# 3_6_1--esp32_-_0730.net
KiCad netlist of a schematic drawn in EasyEDA Pro
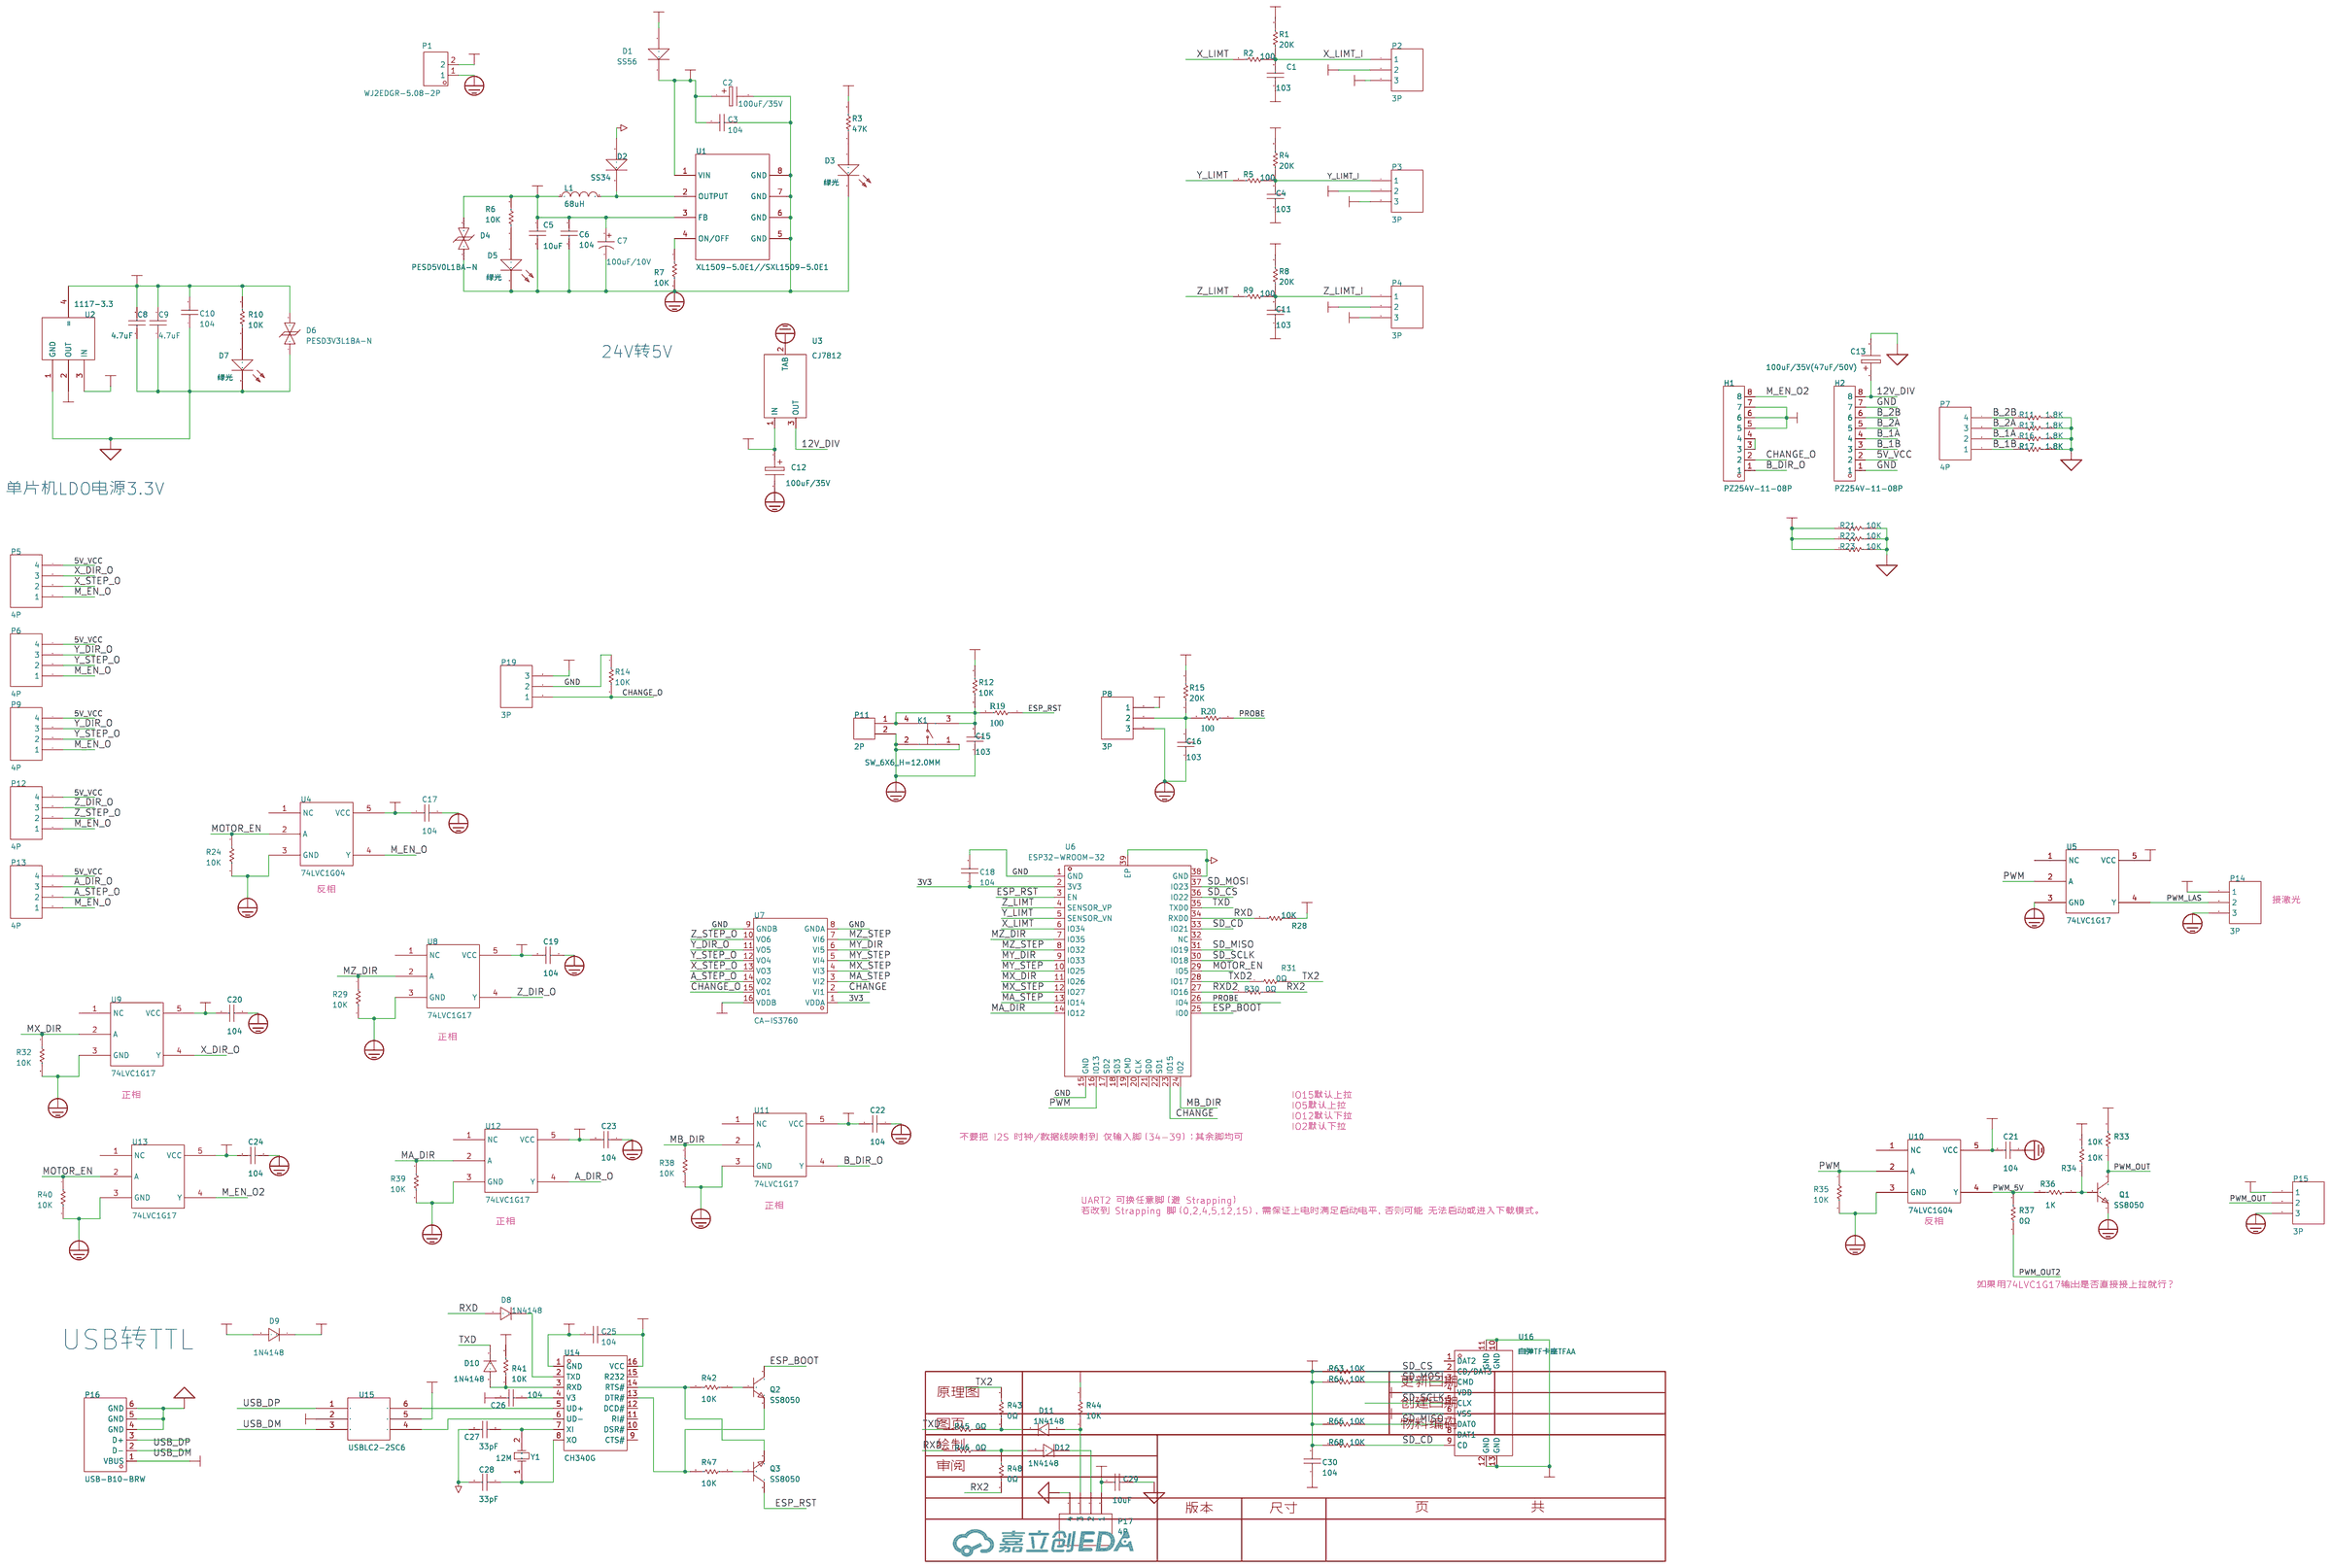
[diagram p0: schematic sheet]

(export (version "E")
  (design (tool "Eeschema 10.0.6"))
  (components
    (comp (ref "C1") (value "103") (footprint "easyedapro:11") (libsource (lib "easyedapro") (part "CAP")))
    (comp (ref "C2")
      (value "100uF/35V")
      (footprint "easyedapro:电解电容贴片10x10")
      (libsource (lib "easyedapro") (part "ELECTRO1"))
    )
    (comp (ref "C3")
      (value "104")
      (footprint "easyedapro:0603C")
      (description "Capacitor (Semiconductor SIM Model)")
      (libsource (lib "easyedapro") (part "Cap Semi"))
    )
    (comp (ref "C4") (value "103") (footprint "easyedapro:11") (libsource (lib "easyedapro") (part "CAP")))
    (comp (ref "C5") (value "10uF") (libsource (lib "") (part "CAP_1")))
    (comp (ref "C6")
      (value "104")
      (footprint "easyedapro:0603C")
      (description "Capacitor (Semiconductor SIM Model)")
      (libsource (lib "easyedapro") (part "Cap Semi"))
    )
    (comp (ref "C7")
      (value "100uF/10V")
      (footprint "easyedapro:CAP-SMD_BD5.0-L5.3-W5.3-RD")
      (fields (field (name "Manufacturer Part") "CS1A101M-CRD54") (field (name "Manufacturer") "ST(先科)"))
      (libsource (lib "easyedapro") (part "CS1A101M-CRD54"))
    )
    (comp (ref "C8") (value "4.7uF") (libsource (lib "") (part "CAP_1")))
    (comp (ref "C9") (value "4.7uF") (libsource (lib "") (part "CAP_1")))
    (comp (ref "C10")
      (value "104")
      (footprint "easyedapro:0603C")
      (description "Capacitor (Semiconductor SIM Model)")
      (libsource (lib "easyedapro") (part "Cap Semi"))
    )
    (comp (ref "C11") (value "103") (footprint "easyedapro:11") (libsource (lib "easyedapro") (part "CAP")))
    (comp (ref "C12")
      (value "100uF/35V")
      (footprint "easyedapro:电解电容贴片10x10")
      (libsource (lib "easyedapro") (part "ELECTRO1"))
    )
    (comp (ref "C13")
      (value "100uF/35V(47uF/50V)")
      (footprint "easyedapro:电解电容贴片10x10")
      (libsource (lib "easyedapro") (part "ELECTRO1"))
    )
    (comp (ref "C15") (value "103") (footprint "easyedapro:11") (libsource (lib "easyedapro") (part "CAP")))
    (comp (ref "C16") (value "103") (footprint "easyedapro:11") (libsource (lib "easyedapro") (part "CAP")))
    (comp (ref "C17")
      (value "104")
      (footprint "easyedapro:0603C")
      (description "Capacitor (Semiconductor SIM Model)")
      (libsource (lib "easyedapro") (part "Cap Semi"))
    )
    (comp (ref "C18")
      (value "104")
      (footprint "easyedapro:0603C")
      (description "Capacitor (Semiconductor SIM Model)")
      (libsource (lib "easyedapro") (part "Cap Semi"))
    )
    (comp (ref "C19")
      (value "104")
      (footprint "easyedapro:0603C")
      (description "Capacitor (Semiconductor SIM Model)")
      (libsource (lib "easyedapro") (part "Cap Semi"))
    )
    (comp (ref "C20")
      (value "104")
      (footprint "easyedapro:0603C")
      (description "Capacitor (Semiconductor SIM Model)")
      (libsource (lib "easyedapro") (part "Cap Semi"))
    )
    (comp (ref "C21")
      (value "104")
      (footprint "easyedapro:0603C")
      (description "Capacitor (Semiconductor SIM Model)")
      (libsource (lib "easyedapro") (part "Cap Semi"))
    )
    (comp (ref "C22")
      (value "104")
      (footprint "easyedapro:0603C")
      (description "Capacitor (Semiconductor SIM Model)")
      (libsource (lib "easyedapro") (part "Cap Semi"))
    )
    (comp (ref "C23")
      (value "104")
      (footprint "easyedapro:0603C")
      (description "Capacitor (Semiconductor SIM Model)")
      (libsource (lib "easyedapro") (part "Cap Semi"))
    )
    (comp (ref "C24")
      (value "104")
      (footprint "easyedapro:0603C")
      (description "Capacitor (Semiconductor SIM Model)")
      (libsource (lib "easyedapro") (part "Cap Semi"))
    )
    (comp (ref "C25")
      (value "104")
      (footprint "easyedapro:0603C")
      (description "Capacitor (Semiconductor SIM Model)")
      (libsource (lib "easyedapro") (part "Cap Semi"))
    )
    (comp (ref "C26")
      (value "104")
      (footprint "easyedapro:0603C")
      (description "Capacitor (Semiconductor SIM Model)")
      (libsource (lib "easyedapro") (part "Cap Semi"))
    )
    (comp (ref "C27")
      (value "18pF")
      (footprint "easyedapro:0603C")
      (description "Capacitor (Semiconductor SIM Model)")
      (libsource (lib "easyedapro") (part "Cap Semi"))
    )
    (comp (ref "C28")
      (value "18pF")
      (footprint "easyedapro:0603C")
      (description "Capacitor (Semiconductor SIM Model)")
      (libsource (lib "easyedapro") (part "Cap Semi"))
    )
    (comp (ref "C29") (value "10uF") (libsource (lib "") (part "CAP_1")))
    (comp (ref "C30")
      (value "104")
      (footprint "easyedapro:11")
      (description "Capacitor (Semiconductor SIM Model)")
      (libsource (lib "easyedapro") (part "Cap Semi"))
    )
    (comp (ref "D1") (value "SS56") (footprint "easyedapro:SMA") (libsource (lib "") (part "1N4148_1")))
    (comp (ref "D2") (value "SS34") (libsource (lib "easyedapro") (part "1N4148")))
    (comp (ref "D3")
      (value "绿光")
      (footprint "easyedapro:0603LED")
      (libsource (lib "easyedapro") (part "LED"))
    )
    (comp (ref "D4")
      (value "PESD5V0L1BA-N")
      (footprint "easyedapro:SOD-523_L1.2-W0.8-LS1.6-BI")
      (description "极性:Bidirectional;反向关断电压（典型值）:5V (Max);击穿电压（最小值）:6V;箝位电压:15V;峰值脉冲电流（10/1000us）:5A (8/20us);")
      (fields (field (name "Manufacturer") "BORN伯恩半导体"))
      (libsource (lib "easyedapro") (part "PESD5V0S1BBN"))
    )
    (comp (ref "D5")
      (value "绿光")
      (footprint "easyedapro:0603LED")
      (libsource (lib "easyedapro") (part "LED"))
    )
    (comp (ref "D6")
      (value "PESD3V3L1BA-N")
      (footprint "easyedapro:SOD-523_L1.2-W0.8-LS1.6-BI")
      (description "极性:Bidirectional;反向关断电压（典型值）:5V (Max);击穿电压（最小值）:6V;箝位电压:15V;峰值脉冲电流（10/1000us）:5A (8/20us);")
      (fields (field (name "Manufacturer") "BORN伯恩半导体"))
      (libsource (lib "easyedapro") (part "PESD5V0S1BBN"))
    )
    (comp (ref "D7")
      (value "绿光")
      (footprint "easyedapro:0603LED")
      (libsource (lib "easyedapro") (part "LED"))
    )
    (comp (ref "D8")
      (value "1N4148")
      (footprint "easyedapro:SOD-123_L2.8-W1.8-LS3.7-RD")
      (fields (field (name "Manufacturer") "MCC(美微科)"))
      (libsource (lib "easyedapro") (part "1N4148W-TP"))
    )
    (comp (ref "D9")
      (value "1N4148")
      (footprint "easyedapro:SOD-123_L2.8-W1.8-LS3.7-RD")
      (fields (field (name "Manufacturer") "MCC(美微科)"))
      (libsource (lib "easyedapro") (part "1N4148W-TP"))
    )
    (comp (ref "D10")
      (value "1N4148")
      (footprint "easyedapro:SOD-123_L2.8-W1.8-LS3.7-RD")
      (fields (field (name "Manufacturer") "MCC(美微科)"))
      (libsource (lib "easyedapro") (part "1N4148W-TP"))
    )
    (comp (ref "D11")
      (value "1N4148")
      (footprint "easyedapro:SOD-123_L2.8-W1.8-LS3.7-RD")
      (fields (field (name "Manufacturer") "MCC(美微科)"))
      (libsource (lib "easyedapro") (part "1N4148W-TP"))
    )
    (comp (ref "D12")
      (value "1N4148")
      (footprint "easyedapro:SOD-123_L2.8-W1.8-LS3.7-RD")
      (fields (field (name "Manufacturer") "MCC(美微科)"))
      (libsource (lib "easyedapro") (part "1N4148W-TP"))
    )
    (comp (ref "H1")
      (value "PZ254V-11-08P")
      (footprint "easyedapro:HDR-TH_8P-P2.54-V-M")
      (fields (field (name "Manufacturer") "XFCN(兴飞)"))
      (libsource (lib "easyedapro") (part "PZ254V-11-08P"))
    )
    (comp (ref "H2")
      (value "PZ254V-11-08P")
      (footprint "easyedapro:HDR-TH_8P-P2.54-V-M")
      (fields (field (name "Manufacturer") "XFCN(兴飞)"))
      (libsource (lib "easyedapro") (part "PZ254V-11-08P"))
    )
    (comp (ref "K1")
      (value "SW_6X6_H=12.0MM")
      (footprint "easyedapro:KEY-SMD_4P-L6.0-W6.0-P4.50-LS9.0")
      (libsource (lib "easyedapro") (part "SW_6X6_H=12.0MM"))
    )
    (comp (ref "L1")
      (value "68uH")
      (footprint "easyedapro:IND-SMD_L7.0-W7.0_SMDRI74-330MT")
      (description "电感值:33uH;精度:±20%;额定电流:960mA;饱和电流(Isat):1.8A;类型:屏蔽电感;")
      (fields (field (name "Manufacturer Part") "SMDRI74-330MT") (field (name "Manufacturer") "SXN(顺翔诺)"))
      (libsource (lib "easyedapro") (part "SMDRI74-330MT"))
    )
    (comp (ref "P1")
      (value "WJ2EDGR-5.08-2P")
      (footprint "easyedapro:CONN-TH_WJ2EDGR-5.08-2P")
      (description "每排PIN数:2;安装方式:弯针;排数:1;间距:5.08mm;连接器类型:板端/插座-开口;")
      (fields (field (name "Manufacturer") "KANGNEX(康奈克斯电气)"))
      (libsource (lib "easyedapro") (part "WJ2EDGR-5.08-2P"))
    )
    (comp (ref "P2")
      (value "3P")
      (footprint "easyedapro:HDR1X3_CON")
      (libsource (lib "easyedapro") (part "3P"))
    )
    (comp (ref "P3")
      (value "3P")
      (footprint "easyedapro:HDR1X3_CON")
      (libsource (lib "easyedapro") (part "3P"))
    )
    (comp (ref "P4")
      (value "3P")
      (footprint "easyedapro:HDR1X3_CON")
      (libsource (lib "easyedapro") (part "3P"))
    )
    (comp (ref "P5")
      (value "4P")
      (footprint "easyedapro:HDR1X4_CON")
      (libsource (lib "easyedapro") (part "4P"))
    )
    (comp (ref "P6")
      (value "4P")
      (footprint "easyedapro:HDR1X4_CON")
      (libsource (lib "easyedapro") (part "4P"))
    )
    (comp (ref "P7")
      (value "4P")
      (footprint "easyedapro:HDR1X4_CON")
      (libsource (lib "easyedapro") (part "4P"))
    )
    (comp (ref "P8")
      (value "3P")
      (footprint "easyedapro:HDR1X3_CON")
      (libsource (lib "easyedapro") (part "3P"))
    )
    (comp (ref "P9")
      (value "4P")
      (footprint "easyedapro:HDR1X4_CON")
      (libsource (lib "easyedapro") (part "4P"))
    )
    (comp (ref "P11") (value "2P") (libsource (lib "easyedapro") (part "2P")))
    (comp (ref "P12")
      (value "4P")
      (footprint "easyedapro:HDR1X4_CON")
      (libsource (lib "easyedapro") (part "4P"))
    )
    (comp (ref "P13")
      (value "4P")
      (footprint "easyedapro:HDR1X4_CON")
      (libsource (lib "easyedapro") (part "4P"))
    )
    (comp (ref "P14")
      (value "3P")
      (footprint "easyedapro:HDR1X3_CON")
      (libsource (lib "easyedapro") (part "3P"))
    )
    (comp (ref "P15")
      (value "3P")
      (footprint "easyedapro:HDR1X3_CON")
      (libsource (lib "easyedapro") (part "3P"))
    )
    (comp (ref "P16")
      (value "USB-B10-BRW")
      (footprint "easyedapro:USB-B-TH_USB-B10-BRW")
      (fields (field (name "Manufacturer") "XUNPU(讯普)"))
      (libsource (lib "easyedapro") (part "USB-B10-BRW"))
    )
    (comp (ref "P17")
      (value "4P")
      (footprint "easyedapro:HDR1X4_CON")
      (libsource (lib "easyedapro") (part "4P"))
    )
    (comp (ref "P19")
      (value "3P")
      (footprint "easyedapro:HDR1X3_CON")
      (libsource (lib "easyedapro") (part "3P"))
    )
    (comp (ref "Q1")
      (value "SS8050")
      (footprint "easyedapro:SOT-23-3_L2.9-W1.3-P1.90-LS2.4-BR")
      (fields (field (name "Manufacturer") "CJ（江苏长电/长晶）"))
      (libsource (lib "easyedapro") (part "SS8050_C2150"))
    )
    (comp (ref "Q2")
      (value "SS8050")
      (footprint "easyedapro:SOT-23-3_L2.9-W1.3-P1.90-LS2.4-BR")
      (fields (field (name "Manufacturer") "Doeshare(德芯)"))
      (libsource (lib "easyedapro") (part "SS8050_C2931717"))
    )
    (comp (ref "Q3")
      (value "SS8050")
      (footprint "easyedapro:SOT-23-3_L2.9-W1.3-P1.90-LS2.4-BR")
      (fields (field (name "Manufacturer") "Doeshare(德芯)"))
      (libsource (lib "easyedapro") (part "SS8050_C2931717"))
    )
    (comp (ref "R1")
      (value "20K")
      (footprint "easyedapro:10")
      (description "Resistor")
      (libsource (lib "") (part "RES_1"))
    )
    (comp (ref "R2")
      (value "100")
      (footprint "easyedapro:10")
      (description "Resistor")
      (libsource (lib "") (part "RES_1"))
    )
    (comp (ref "R3")
      (value "47K")
      (footprint "easyedapro:0603R")
      (description "Resistor")
      (libsource (lib "") (part "RES_1"))
    )
    (comp (ref "R4")
      (value "20K")
      (footprint "easyedapro:10")
      (description "Resistor")
      (libsource (lib "") (part "RES_1"))
    )
    (comp (ref "R5")
      (value "100")
      (footprint "easyedapro:10")
      (description "Resistor")
      (libsource (lib "") (part "RES_1"))
    )
    (comp (ref "R6")
      (value "10K")
      (footprint "easyedapro:0603R")
      (description "Resistor")
      (libsource (lib "") (part "RES_1"))
    )
    (comp (ref "R7")
      (value "10K")
      (footprint "easyedapro:0603R")
      (description "Resistor")
      (libsource (lib "") (part "RES_1"))
    )
    (comp (ref "R8")
      (value "20K")
      (footprint "easyedapro:10")
      (description "Resistor")
      (libsource (lib "") (part "RES_1"))
    )
    (comp (ref "R9")
      (value "100")
      (footprint "easyedapro:10")
      (description "Resistor")
      (libsource (lib "") (part "RES_1"))
    )
    (comp (ref "R10")
      (value "10K")
      (footprint "easyedapro:0603R")
      (description "Resistor")
      (libsource (lib "") (part "RES_1"))
    )
    (comp (ref "R11")
      (value "10K")
      (footprint "easyedapro:0603R")
      (description "Resistor")
      (libsource (lib "easyedapro") (part "10K"))
    )
    (comp (ref "R12")
      (value "10K")
      (footprint "easyedapro:0603R")
      (description "Resistor")
      (libsource (lib "") (part "RES_1"))
    )
    (comp (ref "R13")
      (value "10K")
      (footprint "easyedapro:0603R")
      (description "Resistor")
      (libsource (lib "easyedapro") (part "10K"))
    )
    (comp (ref "R14")
      (value "10K")
      (footprint "easyedapro:0603R")
      (description "Resistor")
      (libsource (lib "") (part "RES_1"))
    )
    (comp (ref "R15")
      (value "10K")
      (footprint "easyedapro:0603R")
      (description "Resistor")
      (libsource (lib "") (part "RES_1"))
    )
    (comp (ref "R16")
      (value "10K")
      (footprint "easyedapro:0603R")
      (description "Resistor")
      (libsource (lib "easyedapro") (part "10K"))
    )
    (comp (ref "R17")
      (value "10K")
      (footprint "easyedapro:0603R")
      (description "Resistor")
      (libsource (lib "easyedapro") (part "10K"))
    )
    (comp (ref "R19")
      (value "100")
      (description "Resistor")
      (fields (field (name "Publisher") "Altium Limited"))
      (libsource (lib "easyedapro") (part "RES"))
    )
    (comp (ref "R20")
      (value "100")
      (description "Resistor")
      (fields (field (name "Publisher") "Altium Limited"))
      (libsource (lib "easyedapro") (part "RES"))
    )
    (comp (ref "R21")
      (value "10K")
      (footprint "easyedapro:0603R")
      (description "Resistor")
      (libsource (lib "easyedapro") (part "10K"))
    )
    (comp (ref "R22")
      (value "10K")
      (footprint "easyedapro:0603R")
      (description "Resistor")
      (libsource (lib "easyedapro") (part "10K"))
    )
    (comp (ref "R23")
      (value "10K")
      (footprint "easyedapro:0603R")
      (description "Resistor")
      (libsource (lib "easyedapro") (part "10K"))
    )
    (comp (ref "R24")
      (value "10K")
      (description "Resistor")
      (fields (field (name "Publisher") "Altium Limited"))
      (libsource (lib "easyedapro") (part "RES"))
    )
    (comp (ref "R28")
      (value "10K")
      (footprint "easyedapro:0603R")
      (description "Resistor")
      (libsource (lib "") (part "RES_1"))
    )
    (comp (ref "R29")
      (value "10K")
      (description "Resistor")
      (fields (field (name "Publisher") "Altium Limited"))
      (libsource (lib "easyedapro") (part "RES"))
    )
    (comp (ref "R30")
      (value "0Ω")
      (description "Resistor")
      (fields (field (name "Publisher") "Altium Limited"))
      (libsource (lib "easyedapro") (part "RES"))
    )
    (comp (ref "R31")
      (value "0Ω")
      (description "Resistor")
      (fields (field (name "Publisher") "Altium Limited"))
      (libsource (lib "easyedapro") (part "RES"))
    )
    (comp (ref "R32")
      (value "10K")
      (description "Resistor")
      (fields (field (name "Publisher") "Altium Limited"))
      (libsource (lib "easyedapro") (part "RES"))
    )
    (comp (ref "R33")
      (value "10K")
      (description "Resistor")
      (fields (field (name "Publisher") "Altium Limited"))
      (libsource (lib "easyedapro") (part "RES"))
    )
    (comp (ref "R34")
      (value "10K")
      (description "Resistor")
      (fields (field (name "Publisher") "Altium Limited"))
      (libsource (lib "easyedapro") (part "RES"))
    )
    (comp (ref "R35")
      (value "10K")
      (description "Resistor")
      (fields (field (name "Publisher") "Altium Limited"))
      (libsource (lib "easyedapro") (part "RES"))
    )
    (comp (ref "R36")
      (value "1K")
      (description "Resistor")
      (fields (field (name "Publisher") "Altium Limited"))
      (libsource (lib "easyedapro") (part "RES"))
    )
    (comp (ref "R37")
      (value "0Ω")
      (description "Resistor")
      (fields (field (name "Publisher") "Altium Limited"))
      (libsource (lib "easyedapro") (part "RES"))
    )
    (comp (ref "R38")
      (value "10K")
      (description "Resistor")
      (fields (field (name "Publisher") "Altium Limited"))
      (libsource (lib "easyedapro") (part "RES"))
    )
    (comp (ref "R39")
      (value "10K")
      (description "Resistor")
      (fields (field (name "Publisher") "Altium Limited"))
      (libsource (lib "easyedapro") (part "RES"))
    )
    (comp (ref "R40")
      (value "10K")
      (description "Resistor")
      (fields (field (name "Publisher") "Altium Limited"))
      (libsource (lib "easyedapro") (part "RES"))
    )
    (comp (ref "R41")
      (value "10K")
      (footprint "easyedapro:0603R")
      (description "Resistor")
      (libsource (lib "") (part "RES_1"))
    )
    (comp (ref "R42")
      (value "10K")
      (footprint "easyedapro:0603R")
      (description "Resistor")
      (libsource (lib "") (part "RES_1"))
    )
    (comp (ref "R43")
      (value "0Ω")
      (description "Resistor")
      (fields (field (name "Publisher") "Altium Limited"))
      (libsource (lib "easyedapro") (part "RES"))
    )
    (comp (ref "R44")
      (value "10K")
      (footprint "easyedapro:0603R")
      (description "Resistor")
      (libsource (lib "") (part "RES_1"))
    )
    (comp (ref "R45")
      (value "0Ω")
      (description "Resistor")
      (fields (field (name "Publisher") "Altium Limited"))
      (libsource (lib "easyedapro") (part "RES"))
    )
    (comp (ref "R46")
      (value "0Ω")
      (description "Resistor")
      (fields (field (name "Publisher") "Altium Limited"))
      (libsource (lib "easyedapro") (part "RES"))
    )
    (comp (ref "R47")
      (value "10K")
      (footprint "easyedapro:0603R")
      (description "Resistor")
      (libsource (lib "") (part "RES_1"))
    )
    (comp (ref "R48")
      (value "0Ω")
      (description "Resistor")
      (fields (field (name "Publisher") "Altium Limited"))
      (libsource (lib "easyedapro") (part "RES"))
    )
    (comp (ref "R63")
      (value "10K")
      (footprint "easyedapro:10")
      (description "Resistor")
      (libsource (lib "") (part "RES_1"))
    )
    (comp (ref "R64")
      (value "10K")
      (footprint "easyedapro:10")
      (description "Resistor")
      (libsource (lib "") (part "RES_1"))
    )
    (comp (ref "R66")
      (value "10K")
      (footprint "easyedapro:10")
      (description "Resistor")
      (libsource (lib "") (part "RES_1"))
    )
    (comp (ref "R68")
      (value "10K")
      (footprint "easyedapro:10")
      (description "Resistor")
      (libsource (lib "") (part "RES_1"))
    )
    (comp (ref "U1")
      (value "XL1509-5.0E1//SXL1509-5.0E1")
      (footprint "easyedapro:SOIC-8_L5.0-W4.0-P1.27-LS6.0-BL")
      (description "功能类型:降压型;同步整流:-;输出通道数:-;拓扑结构:-;输入电压:-;输出电流(最大值):-;开关频率:-;")
      (fields (field (name "Manufacturer") "XLSEMI(芯龙)"))
      (libsource (lib "easyedapro") (part "XL1509-5.0E1"))
    )
    (comp (ref "U2")
      (value "1117-3.3")
      (footprint "easyedapro:SOT-223")
      (libsource (lib "easyedapro") (part "LM1117"))
    )
    (comp (ref "U3")
      (value "CJ7812")
      (footprint "easyedapro:TO-263-2_L10.1-W9.1-P5.08-LS15.2-TL")
      (description "输出类型:固定;工作电压:35V;输出电压:12V;输出电流:1.5A;电源纹波抑制比(PSRR):71dB@(120Hz);输出极性:正极;")
      (fields (field (name "Manufacturer") "CJ(江苏长电/长晶)"))
      (libsource (lib "easyedapro") (part "CJ7812_C145151"))
    )
    (comp (ref "U4")
      (value "74LVC1G04")
      (footprint "easyedapro:SMD8")
      (libsource (lib "easyedapro") (part "74LVC1G04"))
    )
    (comp (ref "U5")
      (value "74LVC1G17")
      (footprint "easyedapro:SMD8")
      (libsource (lib "easyedapro") (part "74LVC1G04"))
    )
    (comp (ref "U6")
      (value "ESP32-WROOM-32")
      (footprint "easyedapro:WIFIM-SMD_ESP-WROOM-32")
      (description "WiFi+双模蓝牙 双核CPU 网口 顶配MCU 低功耗蓝牙 ESP32系列ESP-WROOM-32模组/ESP-32S 4MB")
      (fields (field (name "Manufacturer") "ESPRESSIF(乐鑫)"))
      (libsource (lib "easyedapro") (part "ESP-WROOM-32"))
    )
    (comp (ref "U7")
      (value "CA-IS3760")
      (footprint "easyedapro:SOIC-16_L9.9-W3.9-P1.27-LS6.0-BL")
      (fields (field (name "Manufacturer") "Chipanalog(川土微)"))
      (libsource (lib "easyedapro") (part "CA-IS3760HN"))
    )
    (comp (ref "U8")
      (value "74LVC1G17")
      (footprint "easyedapro:SMD8")
      (libsource (lib "easyedapro") (part "74LVC1G04"))
    )
    (comp (ref "U9")
      (value "74LVC1G17")
      (footprint "easyedapro:SMD8")
      (libsource (lib "easyedapro") (part "74LVC1G04"))
    )
    (comp (ref "U10")
      (value "74LVC1G04")
      (footprint "easyedapro:SMD8")
      (libsource (lib "easyedapro") (part "74LVC1G04"))
    )
    (comp (ref "U11")
      (value "74LVC1G17")
      (footprint "easyedapro:SMD8")
      (libsource (lib "easyedapro") (part "74LVC1G04"))
    )
    (comp (ref "U12")
      (value "74LVC1G17")
      (footprint "easyedapro:SMD8")
      (libsource (lib "easyedapro") (part "74LVC1G04"))
    )
    (comp (ref "U13")
      (value "74LVC1G17")
      (footprint "easyedapro:SMD8")
      (libsource (lib "easyedapro") (part "74LVC1G04"))
    )
    (comp (ref "U14")
      (value "CH340G")
      (footprint "easyedapro:SOIC-16_L9.9-W3.9-P1.27-LS6.0-BL")
      (description "应用功能:收发器;接口协议:USB 2.0;数据速率:2Mbps;")
      (fields (field (name "Manufacturer") "WCH(南京沁恒)"))
      (libsource (lib "easyedapro") (part "CH340G"))
    )
    (comp (ref "U15")
      (value "USBLC2-2SC6")
      (footprint "easyedapro:SOT-23-6")
      (libsource (lib "easyedapro") (part "DIP6"))
    )
    (comp (ref "U16")
      (value "自弹TF卡座TFAA")
      (footprint "easyedapro:SIM-SMD_C9900015645")
      (libsource (lib "easyedapro") (part "自弹TF卡座TFAA"))
    )
    (comp (ref "Y1")
      (value "12M")
      (footprint "easyedapro:晶振贴片49SSMD")
      (description "Crystal Oscillator")
      (libsource (lib "easyedapro") (part "XTAL"))
    )
  )
  (nets
    (net (code "1") (name "/12V_DIV") (class "Default")
      (node (ref "C13") (pin "1") (pintype "unspecified"))
      (node (ref "H2") (pin "8") (pinfunction "8_8") (pintype "unspecified"))
      (node (ref "U3") (pin "3") (pinfunction "OUT_3") (pintype "unspecified"))
    )
    (net (code "2") (name "/A_DIR_O") (class "Default")
      (node (ref "P13") (pin "3") (pinfunction "3_3") (pintype "unspecified"))
      (node (ref "U12") (pin "4") (pinfunction "Y_4") (pintype "unspecified"))
    )
    (net (code "3") (name "/A_STEP_O") (class "Default")
      (node (ref "P13") (pin "2") (pinfunction "2_2") (pintype "unspecified"))
      (node (ref "U7") (pin "14") (pinfunction "VO2_14") (pintype "unspecified"))
    )
    (net (code "4") (name "/B_1A") (class "Default")
      (node (ref "H2") (pin "4") (pinfunction "4_4") (pintype "unspecified"))
      (node (ref "P7") (pin "2") (pinfunction "2_2") (pintype "unspecified"))
      (node (ref "R16") (pin "1") (pinfunction "1_1") (pintype "unspecified"))
    )
    (net (code "5") (name "/B_1B") (class "Default")
      (node (ref "H2") (pin "3") (pinfunction "3_3") (pintype "unspecified"))
      (node (ref "P7") (pin "1") (pinfunction "1_1") (pintype "unspecified"))
      (node (ref "R17") (pin "1") (pinfunction "1_1") (pintype "unspecified"))
    )
    (net (code "6") (name "/B_2A") (class "Default")
      (node (ref "H2") (pin "5") (pinfunction "5_5") (pintype "unspecified"))
      (node (ref "P7") (pin "3") (pinfunction "3_3") (pintype "unspecified"))
      (node (ref "R13") (pin "1") (pinfunction "1_1") (pintype "unspecified"))
    )
    (net (code "7") (name "/B_2B") (class "Default")
      (node (ref "H2") (pin "6") (pinfunction "6_6") (pintype "unspecified"))
      (node (ref "P7") (pin "4") (pinfunction "4_4") (pintype "unspecified"))
      (node (ref "R11") (pin "1") (pinfunction "1_1") (pintype "unspecified"))
    )
    (net (code "8") (name "/B_DIR_O") (class "Default")
      (node (ref "H1") (pin "1") (pinfunction "1_1") (pintype "unspecified"))
      (node (ref "U11") (pin "4") (pinfunction "Y_4") (pintype "unspecified"))
    )
    (net (code "9") (name "/CHANGE") (class "Default")
      (node (ref "U6") (pin "23") (pinfunction "IO15_23") (pintype "unspecified"))
      (node (ref "U7") (pin "2") (pinfunction "VI1_2") (pintype "unspecified"))
    )
    (net (code "10") (name "/CHANGE_O") (class "Default")
      (node (ref "H1") (pin "2") (pinfunction "2_2") (pintype "unspecified"))
      (node (ref "P19") (pin "1") (pinfunction "1_1") (pintype "unspecified"))
      (node (ref "R14") (pin "2") (pinfunction "2_2") (pintype "unspecified"))
      (node (ref "U7") (pin "15") (pinfunction "VO1_15") (pintype "unspecified"))
    )
    (net (code "11") (name "/ESP_BOOT") (class "Default")
      (node (ref "Q2") (pin "3") (pinfunction "C_3") (pintype "unspecified"))
      (node (ref "U6") (pin "25") (pinfunction "IO0_25") (pintype "unspecified"))
    )
    (net (code "12") (name "/ESP_RST") (class "Default")
      (node (ref "Q3") (pin "3") (pinfunction "C_3") (pintype "unspecified"))
      (node (ref "R19") (pin "1") (pinfunction "1_1") (pintype "input"))
      (node (ref "U6") (pin "3") (pinfunction "EN_3") (pintype "unspecified"))
    )
    (net (code "13") (name "/MA_DIR") (class "Default")
      (node (ref "R39") (pin "1") (pinfunction "1_1") (pintype "input"))
      (node (ref "U12") (pin "2") (pinfunction "A_2") (pintype "unspecified"))
      (node (ref "U6") (pin "14") (pinfunction "IO12_14") (pintype "unspecified"))
    )
    (net (code "14") (name "/MA_STEP") (class "Default")
      (node (ref "U6") (pin "13") (pinfunction "IO14_13") (pintype "unspecified"))
      (node (ref "U7") (pin "3") (pinfunction "VI2_3") (pintype "unspecified"))
    )
    (net (code "15") (name "/MB_DIR") (class "Default")
      (node (ref "R38") (pin "1") (pinfunction "1_1") (pintype "input"))
      (node (ref "U11") (pin "2") (pinfunction "A_2") (pintype "unspecified"))
      (node (ref "U6") (pin "24") (pinfunction "IO2_24") (pintype "unspecified"))
    )
    (net (code "16") (name "/MOTOR_EN") (class "Default")
      (node (ref "R24") (pin "1") (pinfunction "1_1") (pintype "input"))
      (node (ref "R40") (pin "1") (pinfunction "1_1") (pintype "input"))
      (node (ref "U13") (pin "2") (pinfunction "A_2") (pintype "unspecified"))
      (node (ref "U4") (pin "2") (pinfunction "A_2") (pintype "unspecified"))
      (node (ref "U6") (pin "29") (pinfunction "IO5_29") (pintype "unspecified"))
    )
    (net (code "17") (name "/MX_DIR") (class "Default")
      (node (ref "R32") (pin "1") (pinfunction "1_1") (pintype "input"))
      (node (ref "U6") (pin "11") (pinfunction "IO26_11") (pintype "unspecified"))
      (node (ref "U9") (pin "2") (pinfunction "A_2") (pintype "unspecified"))
    )
    (net (code "18") (name "/MX_STEP") (class "Default")
      (node (ref "U6") (pin "12") (pinfunction "IO27_12") (pintype "unspecified"))
      (node (ref "U7") (pin "4") (pinfunction "VI3_4") (pintype "unspecified"))
    )
    (net (code "19") (name "/MY_DIR") (class "Default")
      (node (ref "U6") (pin "9") (pinfunction "IO33_9") (pintype "unspecified"))
      (node (ref "U7") (pin "6") (pinfunction "VI5_6") (pintype "unspecified"))
    )
    (net (code "20") (name "/MY_STEP") (class "Default")
      (node (ref "U6") (pin "10") (pinfunction "IO25_10") (pintype "unspecified"))
      (node (ref "U7") (pin "5") (pinfunction "VI4_5") (pintype "unspecified"))
    )
    (net (code "21") (name "/MZ_DIR") (class "Default")
      (node (ref "R29") (pin "1") (pinfunction "1_1") (pintype "input"))
      (node (ref "U6") (pin "7") (pinfunction "IO35_7") (pintype "unspecified"))
      (node (ref "U8") (pin "2") (pinfunction "A_2") (pintype "unspecified"))
    )
    (net (code "22") (name "/MZ_STEP") (class "Default")
      (node (ref "U6") (pin "8") (pinfunction "IO32_8") (pintype "unspecified"))
      (node (ref "U7") (pin "7") (pinfunction "VI6_7") (pintype "unspecified"))
    )
    (net (code "23") (name "/M_EN_O") (class "Default")
      (node (ref "P12") (pin "1") (pinfunction "1_1") (pintype "unspecified"))
      (node (ref "P13") (pin "1") (pinfunction "1_1") (pintype "unspecified"))
      (node (ref "P5") (pin "1") (pinfunction "1_1") (pintype "unspecified"))
      (node (ref "P6") (pin "1") (pinfunction "1_1") (pintype "unspecified"))
      (node (ref "P9") (pin "1") (pinfunction "1_1") (pintype "unspecified"))
      (node (ref "U4") (pin "4") (pinfunction "Y_4") (pintype "unspecified"))
    )
    (net (code "24") (name "/M_EN_O2") (class "Default")
      (node (ref "H1") (pin "8") (pinfunction "8_8") (pintype "unspecified"))
      (node (ref "U13") (pin "4") (pinfunction "Y_4") (pintype "unspecified"))
    )
    (net (code "25") (name "/PROBE") (class "Default")
      (node (ref "R20") (pin "1") (pinfunction "1_1") (pintype "input"))
      (node (ref "U6") (pin "26") (pinfunction "IO4_26") (pintype "unspecified"))
    )
    (net (code "26") (name "/PWM") (class "Default")
      (node (ref "R35") (pin "1") (pinfunction "1_1") (pintype "input"))
      (node (ref "U10") (pin "2") (pinfunction "A_2") (pintype "unspecified"))
      (node (ref "U5") (pin "2") (pinfunction "A_2") (pintype "unspecified"))
      (node (ref "U6") (pin "16") (pinfunction "IO13_16") (pintype "unspecified"))
    )
    (net (code "27") (name "/PWM_5V") (class "Default")
      (node (ref "R36") (pin "1") (pinfunction "1_1") (pintype "input"))
      (node (ref "R37") (pin "2") (pinfunction "2_2") (pintype "input"))
      (node (ref "U10") (pin "4") (pinfunction "Y_4") (pintype "unspecified"))
    )
    (net (code "28") (name "/PWM_LAS") (class "Default")
      (node (ref "P14") (pin "2") (pinfunction "2_2") (pintype "unspecified"))
      (node (ref "U5") (pin "4") (pinfunction "Y_4") (pintype "unspecified"))
    )
    (net (code "29") (name "/PWM_OUT") (class "Default")
      (node (ref "P15") (pin "2") (pinfunction "2_2") (pintype "unspecified"))
      (node (ref "Q1") (pin "3") (pinfunction "C_3") (pintype "input"))
      (node (ref "R33") (pin "1") (pinfunction "1_1") (pintype "input"))
    )
    (net (code "30") (name "/PWM_OUT2") (class "Default")
      (node (ref "R37") (pin "1") (pinfunction "1_1") (pintype "input"))
    )
    (net (code "31") (name "/RX2") (class "Default")
      (node (ref "R30") (pin "2") (pinfunction "2_2") (pintype "input"))
      (node (ref "R48") (pin "1") (pinfunction "1_1") (pintype "input"))
    )
    (net (code "32") (name "/RXD") (class "Default")
      (node (ref "D8") (pin "2") (pinfunction "A_2") (pintype "input"))
      (node (ref "R28") (pin "2") (pinfunction "2_2") (pintype "unspecified"))
      (node (ref "R46") (pin "1") (pinfunction "1_1") (pintype "input"))
      (node (ref "U6") (pin "34") (pinfunction "RXD0_34") (pintype "unspecified"))
    )
    (net (code "33") (name "/RXD2") (class "Default")
      (node (ref "R30") (pin "1") (pinfunction "1_1") (pintype "input"))
      (node (ref "U6") (pin "27") (pinfunction "IO16_27") (pintype "unspecified"))
    )
    (net (code "34") (name "/SD_CD") (class "Default")
      (node (ref "R68") (pin "1") (pinfunction "1_1") (pintype "unspecified"))
      (node (ref "U16") (pin "9") (pinfunction "CD_9") (pintype "unspecified"))
      (node (ref "U6") (pin "33") (pinfunction "IO21_33") (pintype "unspecified"))
    )
    (net (code "35") (name "/SD_CS") (class "Default")
      (node (ref "R63") (pin "1") (pinfunction "1_1") (pintype "unspecified"))
      (node (ref "U16") (pin "2") (pinfunction "CD/DAT3_2") (pintype "unspecified"))
      (node (ref "U6") (pin "36") (pinfunction "IO22_36") (pintype "unspecified"))
    )
    (net (code "36") (name "/SD_MISO") (class "Default")
      (node (ref "R66") (pin "1") (pinfunction "1_1") (pintype "unspecified"))
      (node (ref "U16") (pin "7") (pinfunction "DAT0_7") (pintype "unspecified"))
      (node (ref "U6") (pin "31") (pinfunction "IO19_31") (pintype "unspecified"))
    )
    (net (code "37") (name "/SD_MOSI") (class "Default")
      (node (ref "R64") (pin "1") (pinfunction "1_1") (pintype "unspecified"))
      (node (ref "U16") (pin "3") (pinfunction "CMD_3") (pintype "unspecified"))
      (node (ref "U6") (pin "37") (pinfunction "IO23_37") (pintype "unspecified"))
    )
    (net (code "38") (name "/SD_SCLK") (class "Default")
      (node (ref "U16") (pin "5") (pinfunction "CLX_5") (pintype "unspecified"))
      (node (ref "U6") (pin "30") (pinfunction "IO18_30") (pintype "unspecified"))
    )
    (net (code "39") (name "/TX2") (class "Default")
      (node (ref "R31") (pin "2") (pinfunction "2_2") (pintype "input"))
      (node (ref "R43") (pin "2") (pinfunction "2_2") (pintype "input"))
    )
    (net (code "40") (name "/TXD") (class "Default")
      (node (ref "D10") (pin "1") (pinfunction "c_1") (pintype "input"))
      (node (ref "R45") (pin "1") (pinfunction "1_1") (pintype "input"))
      (node (ref "U6") (pin "35") (pinfunction "TXD0_35") (pintype "unspecified"))
    )
    (net (code "41") (name "/TXD2") (class "Default")
      (node (ref "R31") (pin "1") (pinfunction "1_1") (pintype "input"))
      (node (ref "U6") (pin "28") (pinfunction "IO17_28") (pintype "unspecified"))
    )
    (net (code "42") (name "/USB_DM") (class "Default")
      (node (ref "P16") (pin "2") (pinfunction "D-_2") (pintype "unspecified"))
      (node (ref "U15") (pin "3") (pinfunction "3_3") (pintype "unspecified"))
    )
    (net (code "43") (name "/USB_DP") (class "Default")
      (node (ref "P16") (pin "3") (pinfunction "D+_3") (pintype "unspecified"))
      (node (ref "U15") (pin "1") (pinfunction "1_1") (pintype "unspecified"))
    )
    (net (code "44") (name "/X_DIR_O") (class "Default")
      (node (ref "P5") (pin "3") (pinfunction "3_3") (pintype "unspecified"))
      (node (ref "U9") (pin "4") (pinfunction "Y_4") (pintype "unspecified"))
    )
    (net (code "45") (name "/X_LIMT") (class "Default")
      (node (ref "R2") (pin "2") (pinfunction "2_2") (pintype "unspecified"))
      (node (ref "U6") (pin "6") (pinfunction "IO34_6") (pintype "unspecified"))
    )
    (net (code "46") (name "/X_LIMT_I") (class "Default")
      (node (ref "C1") (pin "2") (pinfunction "2_2") (pintype "unspecified"))
      (node (ref "P2") (pin "1") (pinfunction "1_1") (pintype "unspecified"))
      (node (ref "R1") (pin "1") (pinfunction "1_1") (pintype "unspecified"))
      (node (ref "R2") (pin "1") (pinfunction "1_1") (pintype "unspecified"))
    )
    (net (code "47") (name "/X_STEP_O") (class "Default")
      (node (ref "P5") (pin "2") (pinfunction "2_2") (pintype "unspecified"))
      (node (ref "U7") (pin "13") (pinfunction "VO3_13") (pintype "unspecified"))
    )
    (net (code "48") (name "/Y_DIR_O") (class "Default")
      (node (ref "P6") (pin "3") (pinfunction "3_3") (pintype "unspecified"))
      (node (ref "P9") (pin "3") (pinfunction "3_3") (pintype "unspecified"))
      (node (ref "U7") (pin "11") (pinfunction "VO5_11") (pintype "unspecified"))
    )
    (net (code "49") (name "/Y_LIMT") (class "Default")
      (node (ref "R5") (pin "2") (pinfunction "2_2") (pintype "unspecified"))
      (node (ref "U6") (pin "5") (pinfunction "SENSOR_VN_5") (pintype "unspecified"))
    )
    (net (code "50") (name "/Y_LIMT_I") (class "Default")
      (node (ref "C4") (pin "2") (pinfunction "2_2") (pintype "unspecified"))
      (node (ref "P3") (pin "1") (pinfunction "1_1") (pintype "unspecified"))
      (node (ref "R4") (pin "1") (pinfunction "1_1") (pintype "unspecified"))
      (node (ref "R5") (pin "1") (pinfunction "1_1") (pintype "unspecified"))
    )
    (net (code "51") (name "/Y_STEP_O") (class "Default")
      (node (ref "P6") (pin "2") (pinfunction "2_2") (pintype "unspecified"))
      (node (ref "P9") (pin "2") (pinfunction "2_2") (pintype "unspecified"))
      (node (ref "U7") (pin "12") (pinfunction "VO4_12") (pintype "unspecified"))
    )
    (net (code "52") (name "/Z_DIR_O") (class "Default")
      (node (ref "P12") (pin "3") (pinfunction "3_3") (pintype "unspecified"))
      (node (ref "U8") (pin "4") (pinfunction "Y_4") (pintype "unspecified"))
    )
    (net (code "53") (name "/Z_LIMT") (class "Default")
      (node (ref "R9") (pin "2") (pinfunction "2_2") (pintype "unspecified"))
      (node (ref "U6") (pin "4") (pinfunction "SENSOR_VP_4") (pintype "unspecified"))
    )
    (net (code "54") (name "/Z_LIMT_I") (class "Default")
      (node (ref "C11") (pin "2") (pinfunction "2_2") (pintype "unspecified"))
      (node (ref "P4") (pin "1") (pinfunction "1_1") (pintype "unspecified"))
      (node (ref "R8") (pin "1") (pinfunction "1_1") (pintype "unspecified"))
      (node (ref "R9") (pin "1") (pinfunction "1_1") (pintype "unspecified"))
    )
    (net (code "55") (name "/Z_STEP_O") (class "Default")
      (node (ref "P12") (pin "2") (pinfunction "2_2") (pintype "unspecified"))
      (node (ref "U7") (pin "10") (pinfunction "VO6_10") (pintype "unspecified"))
    )
    (net (code "56") (name "3V3") (class "Default")
      (node (ref "C10") (pin "2") (pinfunction "2_2") (pintype "unspecified"))
      (node (ref "C18") (pin "1") (pinfunction "1_1") (pintype "unspecified"))
      (node (ref "C30") (pin "2") (pinfunction "2_2") (pintype "unspecified"))
      (node (ref "C8") (pin "2") (pinfunction "2_2") (pintype "input"))
      (node (ref "C9") (pin "2") (pinfunction "2_2") (pintype "input"))
      (node (ref "D6") (pin "2") (pinfunction "2_2") (pintype "input"))
      (node (ref "R10") (pin "2") (pinfunction "2_2") (pintype "unspecified"))
      (node (ref "R12") (pin "1") (pinfunction "1_1") (pintype "unspecified"))
      (node (ref "R28") (pin "1") (pinfunction "1_1") (pintype "unspecified"))
      (node (ref "R63") (pin "2") (pinfunction "2_2") (pintype "unspecified"))
      (node (ref "R64") (pin "2") (pinfunction "2_2") (pintype "unspecified"))
      (node (ref "R66") (pin "2") (pinfunction "2_2") (pintype "unspecified"))
      (node (ref "R68") (pin "2") (pinfunction "2_2") (pintype "unspecified"))
      (node (ref "U16") (pin "4") (pinfunction "VDD_4") (pintype "unspecified"))
      (node (ref "U2") (pin "2") (pinfunction "OUT_2") (pintype "unspecified"))
      (node (ref "U2") (pin "4") (pinfunction "=_4") (pintype "unspecified"))
      (node (ref "U6") (pin "2") (pinfunction "3V3_2") (pintype "unspecified"))
      (node (ref "U7") (pin "1") (pinfunction "VDDA_1") (pintype "unspecified"))
    )
    (net (code "57") (name "5V_VCC") (class "Default")
      (node (ref "C17") (pin "2") (pinfunction "2_2") (pintype "unspecified"))
      (node (ref "C19") (pin "2") (pinfunction "2_2") (pintype "unspecified"))
      (node (ref "C20") (pin "2") (pinfunction "2_2") (pintype "unspecified"))
      (node (ref "C21") (pin "2") (pinfunction "2_2") (pintype "unspecified"))
      (node (ref "C22") (pin "2") (pinfunction "2_2") (pintype "unspecified"))
      (node (ref "C23") (pin "2") (pinfunction "2_2") (pintype "unspecified"))
      (node (ref "C24") (pin "2") (pinfunction "2_2") (pintype "unspecified"))
      (node (ref "C25") (pin "1") (pinfunction "1_1") (pintype "unspecified"))
      (node (ref "C29") (pin "1") (pinfunction "1_1") (pintype "input"))
      (node (ref "C5") (pin "1") (pinfunction "1_1") (pintype "input"))
      (node (ref "C6") (pin "2") (pinfunction "2_2") (pintype "unspecified"))
      (node (ref "C7") (pin "1") (pinfunction "1_1") (pintype "input"))
      (node (ref "D4") (pin "2") (pinfunction "2_2") (pintype "input"))
      (node (ref "D9") (pin "1") (pinfunction "c_1") (pintype "input"))
      (node (ref "H1") (pin "5") (pinfunction "5_5") (pintype "unspecified"))
      (node (ref "H1") (pin "6") (pinfunction "6_6") (pintype "unspecified"))
      (node (ref "H1") (pin "7") (pinfunction "7_7") (pintype "unspecified"))
      (node (ref "H2") (pin "2") (pinfunction "2_2") (pintype "unspecified"))
      (node (ref "L1") (pin "1") (pinfunction "1_1") (pintype "unspecified"))
      (node (ref "P12") (pin "4") (pinfunction "4_4") (pintype "unspecified"))
      (node (ref "P13") (pin "4") (pinfunction "4_4") (pintype "unspecified"))
      (node (ref "P15") (pin "1") (pinfunction "1_1") (pintype "unspecified"))
      (node (ref "P17") (pin "1") (pinfunction "1_1") (pintype "unspecified"))
      (node (ref "P19") (pin "3") (pinfunction "3_3") (pintype "unspecified"))
      (node (ref "P2") (pin "3") (pinfunction "3_3") (pintype "unspecified"))
      (node (ref "P3") (pin "3") (pinfunction "3_3") (pintype "unspecified"))
      (node (ref "P4") (pin "3") (pinfunction "3_3") (pintype "unspecified"))
      (node (ref "P5") (pin "4") (pinfunction "4_4") (pintype "unspecified"))
      (node (ref "P6") (pin "4") (pinfunction "4_4") (pintype "unspecified"))
      (node (ref "P8") (pin "1") (pinfunction "1_1") (pintype "unspecified"))
      (node (ref "P9") (pin "4") (pinfunction "4_4") (pintype "unspecified"))
      (node (ref "R1") (pin "2") (pinfunction "2_2") (pintype "unspecified"))
      (node (ref "R15") (pin "1") (pinfunction "1_1") (pintype "unspecified"))
      (node (ref "R21") (pin "1") (pinfunction "1_1") (pintype "unspecified"))
      (node (ref "R22") (pin "1") (pinfunction "1_1") (pintype "unspecified"))
      (node (ref "R23") (pin "1") (pinfunction "1_1") (pintype "unspecified"))
      (node (ref "R33") (pin "2") (pinfunction "2_2") (pintype "input"))
      (node (ref "R34") (pin "2") (pinfunction "2_2") (pintype "input"))
      (node (ref "R4") (pin "2") (pinfunction "2_2") (pintype "unspecified"))
      (node (ref "R41") (pin "2") (pinfunction "2_2") (pintype "unspecified"))
      (node (ref "R44") (pin "2") (pinfunction "2_2") (pintype "unspecified"))
      (node (ref "R6") (pin "2") (pinfunction "2_2") (pintype "unspecified"))
      (node (ref "R8") (pin "2") (pinfunction "2_2") (pintype "unspecified"))
      (node (ref "U1") (pin "3") (pinfunction "FB_3") (pintype "input"))
      (node (ref "U10") (pin "5") (pinfunction "VCC_5") (pintype "unspecified"))
      (node (ref "U11") (pin "5") (pinfunction "VCC_5") (pintype "unspecified"))
      (node (ref "U12") (pin "5") (pinfunction "VCC_5") (pintype "unspecified"))
      (node (ref "U13") (pin "5") (pinfunction "VCC_5") (pintype "unspecified"))
      (node (ref "U14") (pin "16") (pinfunction "VCC_16") (pintype "unspecified"))
      (node (ref "U2") (pin "3") (pinfunction "IN_3") (pintype "unspecified"))
      (node (ref "U4") (pin "5") (pinfunction "VCC_5") (pintype "unspecified"))
      (node (ref "U5") (pin "5") (pinfunction "VCC_5") (pintype "unspecified"))
      (node (ref "U7") (pin "16") (pinfunction "VDDB_16") (pintype "unspecified"))
      (node (ref "U8") (pin "5") (pinfunction "VCC_5") (pintype "unspecified"))
      (node (ref "U9") (pin "5") (pinfunction "VCC_5") (pintype "unspecified"))
    )
    (net (code "58") (name "24V") (class "Default")
      (node (ref "C12") (pin "1") (pintype "unspecified"))
      (node (ref "D1") (pin "1") (pinfunction "1_1") (pintype "unspecified"))
      (node (ref "P1") (pin "2") (pinfunction "2_2") (pintype "input"))
      (node (ref "P14") (pin "1") (pinfunction "1_1") (pintype "unspecified"))
      (node (ref "R3") (pin "2") (pinfunction "2_2") (pintype "unspecified"))
      (node (ref "U3") (pin "1") (pinfunction "IN_1") (pintype "unspecified"))
    )
    (net (code "59") (name "GND") (class "Default")
      (node (ref "C1") (pin "1") (pinfunction "1_1") (pintype "unspecified"))
      (node (ref "C10") (pin "1") (pinfunction "1_1") (pintype "unspecified"))
      (node (ref "C11") (pin "1") (pinfunction "1_1") (pintype "unspecified"))
      (node (ref "C12") (pin "2") (pintype "unspecified"))
      (node (ref "C13") (pin "2") (pintype "unspecified"))
      (node (ref "C15") (pin "1") (pinfunction "1_1") (pintype "unspecified"))
      (node (ref "C16") (pin "1") (pinfunction "1_1") (pintype "unspecified"))
      (node (ref "C17") (pin "1") (pinfunction "1_1") (pintype "unspecified"))
      (node (ref "C18") (pin "2") (pinfunction "2_2") (pintype "unspecified"))
      (node (ref "C19") (pin "1") (pinfunction "1_1") (pintype "unspecified"))
      (node (ref "C2") (pin "2") (pintype "unspecified"))
      (node (ref "C20") (pin "1") (pinfunction "1_1") (pintype "unspecified"))
      (node (ref "C21") (pin "1") (pinfunction "1_1") (pintype "unspecified"))
      (node (ref "C22") (pin "1") (pinfunction "1_1") (pintype "unspecified"))
      (node (ref "C23") (pin "1") (pinfunction "1_1") (pintype "unspecified"))
      (node (ref "C24") (pin "1") (pinfunction "1_1") (pintype "unspecified"))
      (node (ref "C25") (pin "2") (pinfunction "2_2") (pintype "unspecified"))
      (node (ref "C26") (pin "2") (pinfunction "2_2") (pintype "unspecified"))
      (node (ref "C27") (pin "2") (pinfunction "2_2") (pintype "unspecified"))
      (node (ref "C28") (pin "2") (pinfunction "2_2") (pintype "unspecified"))
      (node (ref "C29") (pin "2") (pinfunction "2_2") (pintype "input"))
      (node (ref "C3") (pin "1") (pinfunction "1_1") (pintype "unspecified"))
      (node (ref "C30") (pin "1") (pinfunction "1_1") (pintype "unspecified"))
      (node (ref "C4") (pin "1") (pinfunction "1_1") (pintype "unspecified"))
      (node (ref "C5") (pin "2") (pinfunction "2_2") (pintype "input"))
      (node (ref "C6") (pin "1") (pinfunction "1_1") (pintype "unspecified"))
      (node (ref "C7") (pin "2") (pinfunction "2_2") (pintype "input"))
      (node (ref "C8") (pin "1") (pinfunction "1_1") (pintype "input"))
      (node (ref "C9") (pin "1") (pinfunction "1_1") (pintype "input"))
      (node (ref "D2") (pin "1") (pinfunction "1_1") (pintype "input"))
      (node (ref "D3") (pin "2") (pinfunction "2_2") (pintype "unspecified"))
      (node (ref "D4") (pin "1") (pinfunction "1_1") (pintype "input"))
      (node (ref "D5") (pin "2") (pinfunction "2_2") (pintype "unspecified"))
      (node (ref "D6") (pin "1") (pinfunction "1_1") (pintype "input"))
      (node (ref "D7") (pin "2") (pinfunction "2_2") (pintype "unspecified"))
      (node (ref "H2") (pin "1") (pinfunction "1_1") (pintype "unspecified"))
      (node (ref "H2") (pin "7") (pinfunction "7_7") (pintype "unspecified"))
      (node (ref "K1") (pin "1") (pinfunction "1_1") (pintype "unspecified"))
      (node (ref "K1") (pin "2") (pinfunction "2_2") (pintype "unspecified"))
      (node (ref "P1") (pin "1") (pinfunction "1_1") (pintype "input"))
      (node (ref "P11") (pin "2") (pintype "input"))
      (node (ref "P14") (pin "3") (pinfunction "3_3") (pintype "unspecified"))
      (node (ref "P15") (pin "3") (pinfunction "3_3") (pintype "unspecified"))
      (node (ref "P16") (pin "4") (pinfunction "GND_4") (pintype "unspecified"))
      (node (ref "P16") (pin "5") (pinfunction "GND_5") (pintype "unspecified"))
      (node (ref "P16") (pin "6") (pinfunction "GND_6") (pintype "unspecified"))
      (node (ref "P17") (pin "4") (pinfunction "4_4") (pintype "unspecified"))
      (node (ref "P19") (pin "2") (pinfunction "2_2") (pintype "unspecified"))
      (node (ref "P2") (pin "2") (pinfunction "2_2") (pintype "unspecified"))
      (node (ref "P3") (pin "2") (pinfunction "2_2") (pintype "unspecified"))
      (node (ref "P4") (pin "2") (pinfunction "2_2") (pintype "unspecified"))
      (node (ref "P8") (pin "3") (pinfunction "3_3") (pintype "unspecified"))
      (node (ref "Q1") (pin "2") (pinfunction "E_2") (pintype "input"))
      (node (ref "R11") (pin "2") (pinfunction "2_2") (pintype "unspecified"))
      (node (ref "R13") (pin "2") (pinfunction "2_2") (pintype "unspecified"))
      (node (ref "R14") (pin "1") (pinfunction "1_1") (pintype "unspecified"))
      (node (ref "R16") (pin "2") (pinfunction "2_2") (pintype "unspecified"))
      (node (ref "R17") (pin "2") (pinfunction "2_2") (pintype "unspecified"))
      (node (ref "R21") (pin "2") (pinfunction "2_2") (pintype "unspecified"))
      (node (ref "R22") (pin "2") (pinfunction "2_2") (pintype "unspecified"))
      (node (ref "R23") (pin "2") (pinfunction "2_2") (pintype "unspecified"))
      (node (ref "R24") (pin "2") (pinfunction "2_2") (pintype "input"))
      (node (ref "R29") (pin "2") (pinfunction "2_2") (pintype "input"))
      (node (ref "R32") (pin "2") (pinfunction "2_2") (pintype "input"))
      (node (ref "R35") (pin "2") (pinfunction "2_2") (pintype "input"))
      (node (ref "R38") (pin "2") (pinfunction "2_2") (pintype "input"))
      (node (ref "R39") (pin "2") (pinfunction "2_2") (pintype "input"))
      (node (ref "R40") (pin "2") (pinfunction "2_2") (pintype "input"))
      (node (ref "R7") (pin "2") (pinfunction "2_2") (pintype "unspecified"))
      (node (ref "U1") (pin "5") (pinfunction "GND_5") (pintype "input"))
      (node (ref "U1") (pin "6") (pinfunction "GND_6") (pintype "input"))
      (node (ref "U1") (pin "7") (pinfunction "GND_7") (pintype "input"))
      (node (ref "U1") (pin "8") (pinfunction "GND_8") (pintype "input"))
      (node (ref "U10") (pin "3") (pinfunction "GND_3") (pintype "unspecified"))
      (node (ref "U11") (pin "3") (pinfunction "GND_3") (pintype "unspecified"))
      (node (ref "U12") (pin "3") (pinfunction "GND_3") (pintype "unspecified"))
      (node (ref "U13") (pin "3") (pinfunction "GND_3") (pintype "unspecified"))
      (node (ref "U14") (pin "1") (pinfunction "GND_1") (pintype "unspecified"))
      (node (ref "U15") (pin "2") (pinfunction "2_2") (pintype "unspecified"))
      (node (ref "U16") (pin "10") (pinfunction "GND_10") (pintype "unspecified"))
      (node (ref "U16") (pin "11") (pinfunction "GND_11") (pintype "unspecified"))
      (node (ref "U16") (pin "12") (pinfunction "GND_12") (pintype "unspecified"))
      (node (ref "U16") (pin "13") (pinfunction "GND_13") (pintype "unspecified"))
      (node (ref "U16") (pin "6") (pinfunction "VSS_6") (pintype "unspecified"))
      (node (ref "U2") (pin "1") (pinfunction "GND_1") (pintype "unspecified"))
      (node (ref "U3") (pin "2") (pinfunction "TAB_2") (pintype "unspecified"))
      (node (ref "U4") (pin "3") (pinfunction "GND_3") (pintype "unspecified"))
      (node (ref "U5") (pin "3") (pinfunction "GND_3") (pintype "unspecified"))
      (node (ref "U6") (pin "1") (pinfunction "GND_1") (pintype "unspecified"))
      (node (ref "U6") (pin "15") (pinfunction "GND_15") (pintype "unspecified"))
      (node (ref "U6") (pin "38") (pinfunction "GND_38") (pintype "unspecified"))
      (node (ref "U6") (pin "39") (pinfunction "EP_39") (pintype "unspecified"))
      (node (ref "U7") (pin "8") (pinfunction "GNDA_8") (pintype "unspecified"))
      (node (ref "U7") (pin "9") (pinfunction "GNDB_9") (pintype "unspecified"))
      (node (ref "U8") (pin "3") (pinfunction "GND_3") (pintype "unspecified"))
      (node (ref "U9") (pin "3") (pinfunction "GND_3") (pintype "unspecified"))
    )
    (net (code "60") (name "Net-(C15-Pad2)") (class "Default")
      (node (ref "C15") (pin "2") (pinfunction "2_2") (pintype "unspecified"))
      (node (ref "K1") (pin "3") (pinfunction "3_3") (pintype "unspecified"))
      (node (ref "K1") (pin "4") (pinfunction "4_4") (pintype "unspecified"))
      (node (ref "P11") (pin "1") (pintype "input"))
      (node (ref "R12") (pin "2") (pinfunction "2_2") (pintype "unspecified"))
      (node (ref "R19") (pin "2") (pinfunction "2_2") (pintype "input"))
    )
    (net (code "61") (name "Net-(C16-Pad2)") (class "Default")
      (node (ref "C16") (pin "2") (pinfunction "2_2") (pintype "unspecified"))
      (node (ref "P8") (pin "2") (pinfunction "2_2") (pintype "unspecified"))
      (node (ref "R15") (pin "2") (pinfunction "2_2") (pintype "unspecified"))
      (node (ref "R20") (pin "2") (pinfunction "2_2") (pintype "input"))
    )
    (net (code "62") (name "Net-(D3-Pad1)") (class "Default")
      (node (ref "D3") (pin "1") (pinfunction "1_1") (pintype "unspecified"))
      (node (ref "R3") (pin "1") (pinfunction "1_1") (pintype "unspecified"))
    )
    (net (code "63") (name "Net-(D5-Pad1)") (class "Default")
      (node (ref "D5") (pin "1") (pinfunction "1_1") (pintype "unspecified"))
      (node (ref "R6") (pin "1") (pinfunction "1_1") (pintype "unspecified"))
    )
    (net (code "64") (name "Net-(D7-Pad1)") (class "Default")
      (node (ref "D7") (pin "1") (pinfunction "1_1") (pintype "unspecified"))
      (node (ref "R10") (pin "1") (pinfunction "1_1") (pintype "unspecified"))
    )
    (net (code "65") (name "Net-(D8-c)") (class "Default")
      (node (ref "D8") (pin "1") (pinfunction "c_1") (pintype "input"))
      (node (ref "U14") (pin "2") (pinfunction "TXD_2") (pintype "unspecified"))
    )
    (net (code "66") (name "Net-(D10-A)") (class "Default")
      (node (ref "D10") (pin "2") (pinfunction "A_2") (pintype "input"))
      (node (ref "R41") (pin "1") (pinfunction "1_1") (pintype "unspecified"))
      (node (ref "U14") (pin "3") (pinfunction "RXD_3") (pintype "unspecified"))
    )
    (net (code "67") (name "Net-(D11-A)") (class "Default")
      (node (ref "D11") (pin "2") (pinfunction "A_2") (pintype "input"))
      (node (ref "P17") (pin "3") (pinfunction "3_3") (pintype "unspecified"))
      (node (ref "R44") (pin "1") (pinfunction "1_1") (pintype "unspecified"))
    )
    (net (code "68") (name "Net-(D11-c)") (class "Default")
      (node (ref "D11") (pin "1") (pinfunction "c_1") (pintype "input"))
      (node (ref "R43") (pin "1") (pinfunction "1_1") (pintype "input"))
      (node (ref "R45") (pin "2") (pinfunction "2_2") (pintype "input"))
    )
    (net (code "69") (name "Net-(D12-A)") (class "Default")
      (node (ref "D12") (pin "2") (pinfunction "A_2") (pintype "input"))
      (node (ref "R46") (pin "2") (pinfunction "2_2") (pintype "input"))
      (node (ref "R48") (pin "2") (pinfunction "2_2") (pintype "input"))
    )
    (net (code "70") (name "Net-(D12-c)") (class "Default")
      (node (ref "D12") (pin "1") (pinfunction "c_1") (pintype "input"))
      (node (ref "P17") (pin "2") (pinfunction "2_2") (pintype "unspecified"))
    )
    (net (code "71") (name "Net-(H1-Pad3)") (class "Default")
      (node (ref "H1") (pin "3") (pinfunction "3_3") (pintype "unspecified"))
      (node (ref "H1") (pin "4") (pinfunction "4_4") (pintype "unspecified"))
    )
    (net (code "72") (name "Net-(Q1-B)") (class "Default")
      (node (ref "Q1") (pin "1") (pinfunction "B_1") (pintype "input"))
      (node (ref "R34") (pin "1") (pinfunction "1_1") (pintype "input"))
      (node (ref "R36") (pin "2") (pinfunction "2_2") (pintype "input"))
    )
    (net (code "73") (name "Net-(Q2-B)") (class "Default")
      (node (ref "Q2") (pin "1") (pinfunction "B_1") (pintype "unspecified"))
      (node (ref "R42") (pin "2") (pinfunction "2_2") (pintype "unspecified"))
    )
    (net (code "74") (name "Net-(Q2-E)") (class "Default")
      (node (ref "Q2") (pin "2") (pinfunction "E_2") (pintype "unspecified"))
      (node (ref "R47") (pin "1") (pinfunction "1_1") (pintype "unspecified"))
      (node (ref "U14") (pin "13") (pinfunction "DTR#_13") (pintype "unspecified"))
    )
    (net (code "75") (name "Net-(Q3-B)") (class "Default")
      (node (ref "Q3") (pin "1") (pinfunction "B_1") (pintype "unspecified"))
      (node (ref "R47") (pin "2") (pinfunction "2_2") (pintype "unspecified"))
    )
    (net (code "76") (name "Net-(Q3-E)") (class "Default")
      (node (ref "Q3") (pin "2") (pinfunction "E_2") (pintype "unspecified"))
      (node (ref "R42") (pin "1") (pinfunction "1_1") (pintype "unspecified"))
      (node (ref "U14") (pin "14") (pinfunction "RTS#_14") (pintype "unspecified"))
    )
    (net (code "77") (name "Net-(U1-ON{slash}OFF)") (class "Default")
      (node (ref "R7") (pin "1") (pinfunction "1_1") (pintype "unspecified"))
      (node (ref "U1") (pin "4") (pinfunction "ON/OFF_4") (pintype "input"))
    )
    (net (code "78") (name "Net-(U1-OUTPUT)") (class "Default")
      (node (ref "D2") (pin "2") (pinfunction "2_2") (pintype "input"))
      (node (ref "L1") (pin "2") (pinfunction "2_2") (pintype "unspecified"))
      (node (ref "U1") (pin "2") (pinfunction "OUTPUT_2") (pintype "input"))
    )
    (net (code "79") (name "Net-(U14-UD+)") (class "Default")
      (node (ref "U14") (pin "5") (pinfunction "UD+_5") (pintype "unspecified"))
      (node (ref "U15") (pin "6") (pinfunction "6_6") (pintype "unspecified"))
    )
    (net (code "80") (name "Net-(U14-UD-)") (class "Default")
      (node (ref "U14") (pin "6") (pinfunction "UD-_6") (pintype "unspecified"))
      (node (ref "U15") (pin "4") (pinfunction "4_4") (pintype "unspecified"))
    )
    (net (code "81") (name "Net-(U14-V3)") (class "Default")
      (node (ref "C26") (pin "1") (pinfunction "1_1") (pintype "unspecified"))
      (node (ref "U14") (pin "4") (pinfunction "V3_4") (pintype "unspecified"))
    )
    (net (code "82") (name "Net-(U14-XI)") (class "Default")
      (node (ref "C27") (pin "1") (pinfunction "1_1") (pintype "unspecified"))
      (node (ref "U14") (pin "7") (pinfunction "XI_7") (pintype "unspecified"))
      (node (ref "Y1") (pin "2") (pinfunction "OSC2_2") (pintype "unspecified"))
    )
    (net (code "83") (name "Net-(U14-XO)") (class "Default")
      (node (ref "C28") (pin "1") (pinfunction "1_1") (pintype "unspecified"))
      (node (ref "U14") (pin "8") (pinfunction "XO_8") (pintype "unspecified"))
      (node (ref "Y1") (pin "1") (pinfunction "OSC1_1") (pintype "unspecified"))
    )
    (net (code "84") (name "VIN_24V") (class "Default")
      (node (ref "C2") (pin "1") (pintype "unspecified"))
      (node (ref "C3") (pin "2") (pinfunction "2_2") (pintype "unspecified"))
      (node (ref "D1") (pin "2") (pinfunction "2_2") (pintype "unspecified"))
      (node (ref "U1") (pin "1") (pinfunction "VIN_1") (pintype "input"))
    )
    (net (code "85") (name "VUSB") (class "Default")
      (node (ref "D9") (pin "2") (pinfunction "A_2") (pintype "input"))
      (node (ref "P16") (pin "1") (pinfunction "VBUS_1") (pintype "unspecified"))
      (node (ref "U15") (pin "5") (pinfunction "5_5") (pintype "unspecified"))
    )
    (net (code "86") (name "unconnected-(U4-NC-Pad1)") (class "Default")
      (node (ref "U4") (pin "1") (pinfunction "NC_1") (pintype "unspecified"))
    )
    (net (code "87") (name "unconnected-(U5-NC-Pad1)") (class "Default")
      (node (ref "U5") (pin "1") (pinfunction "NC_1") (pintype "unspecified"))
    )
    (net (code "88") (name "unconnected-(U6-CLK-Pad20)") (class "Default")
      (node (ref "U6") (pin "20") (pinfunction "CLK_20") (pintype "unspecified"))
    )
    (net (code "89") (name "unconnected-(U6-CMD-Pad19)") (class "Default")
      (node (ref "U6") (pin "19") (pinfunction "CMD_19") (pintype "unspecified"))
    )
    (net (code "90") (name "unconnected-(U6-NC-Pad32)") (class "Default")
      (node (ref "U6") (pin "32") (pinfunction "NC_32") (pintype "unspecified"))
    )
    (net (code "91") (name "unconnected-(U6-SD0-Pad21)") (class "Default")
      (node (ref "U6") (pin "21") (pinfunction "SD0_21") (pintype "unspecified"))
    )
    (net (code "92") (name "unconnected-(U6-SD1-Pad22)") (class "Default")
      (node (ref "U6") (pin "22") (pinfunction "SD1_22") (pintype "unspecified"))
    )
    (net (code "93") (name "unconnected-(U6-SD2-Pad17)") (class "Default")
      (node (ref "U6") (pin "17") (pinfunction "SD2_17") (pintype "unspecified"))
    )
    (net (code "94") (name "unconnected-(U6-SD3-Pad18)") (class "Default")
      (node (ref "U6") (pin "18") (pinfunction "SD3_18") (pintype "unspecified"))
    )
    (net (code "95") (name "unconnected-(U8-NC-Pad1)") (class "Default")
      (node (ref "U8") (pin "1") (pinfunction "NC_1") (pintype "unspecified"))
    )
    (net (code "96") (name "unconnected-(U9-NC-Pad1)") (class "Default")
      (node (ref "U9") (pin "1") (pinfunction "NC_1") (pintype "unspecified"))
    )
    (net (code "97") (name "unconnected-(U10-NC-Pad1)") (class "Default")
      (node (ref "U10") (pin "1") (pinfunction "NC_1") (pintype "unspecified"))
    )
    (net (code "98") (name "unconnected-(U11-NC-Pad1)") (class "Default")
      (node (ref "U11") (pin "1") (pinfunction "NC_1") (pintype "unspecified"))
    )
    (net (code "99") (name "unconnected-(U12-NC-Pad1)") (class "Default")
      (node (ref "U12") (pin "1") (pinfunction "NC_1") (pintype "unspecified"))
    )
    (net (code "100") (name "unconnected-(U13-NC-Pad1)") (class "Default")
      (node (ref "U13") (pin "1") (pinfunction "NC_1") (pintype "unspecified"))
    )
    (net (code "101") (name "unconnected-(U14-CTS#-Pad9)") (class "Default")
      (node (ref "U14") (pin "9") (pinfunction "CTS#_9") (pintype "unspecified"))
    )
    (net (code "102") (name "unconnected-(U14-DCD#-Pad12)") (class "Default")
      (node (ref "U14") (pin "12") (pinfunction "DCD#_12") (pintype "unspecified"))
    )
    (net (code "103") (name "unconnected-(U14-DSR#-Pad10)") (class "Default")
      (node (ref "U14") (pin "10") (pinfunction "DSR#_10") (pintype "unspecified"))
    )
    (net (code "104") (name "unconnected-(U14-R232-Pad15)") (class "Default")
      (node (ref "U14") (pin "15") (pinfunction "R232_15") (pintype "unspecified"))
    )
    (net (code "105") (name "unconnected-(U14-RI#-Pad11)") (class "Default")
      (node (ref "U14") (pin "11") (pinfunction "RI#_11") (pintype "unspecified"))
    )
    (net (code "106") (name "unconnected-(U16-DAT1-Pad8)") (class "Default")
      (node (ref "U16") (pin "8") (pinfunction "DAT1_8") (pintype "unspecified"))
    )
    (net (code "107") (name "unconnected-(U16-DAT2-Pad1)") (class "Default")
      (node (ref "U16") (pin "1") (pinfunction "DAT2_1") (pintype "unspecified"))
    )
  )
)
